# ETH_IFC.net
KiCad netlist of a schematic drawn in Altium Designer
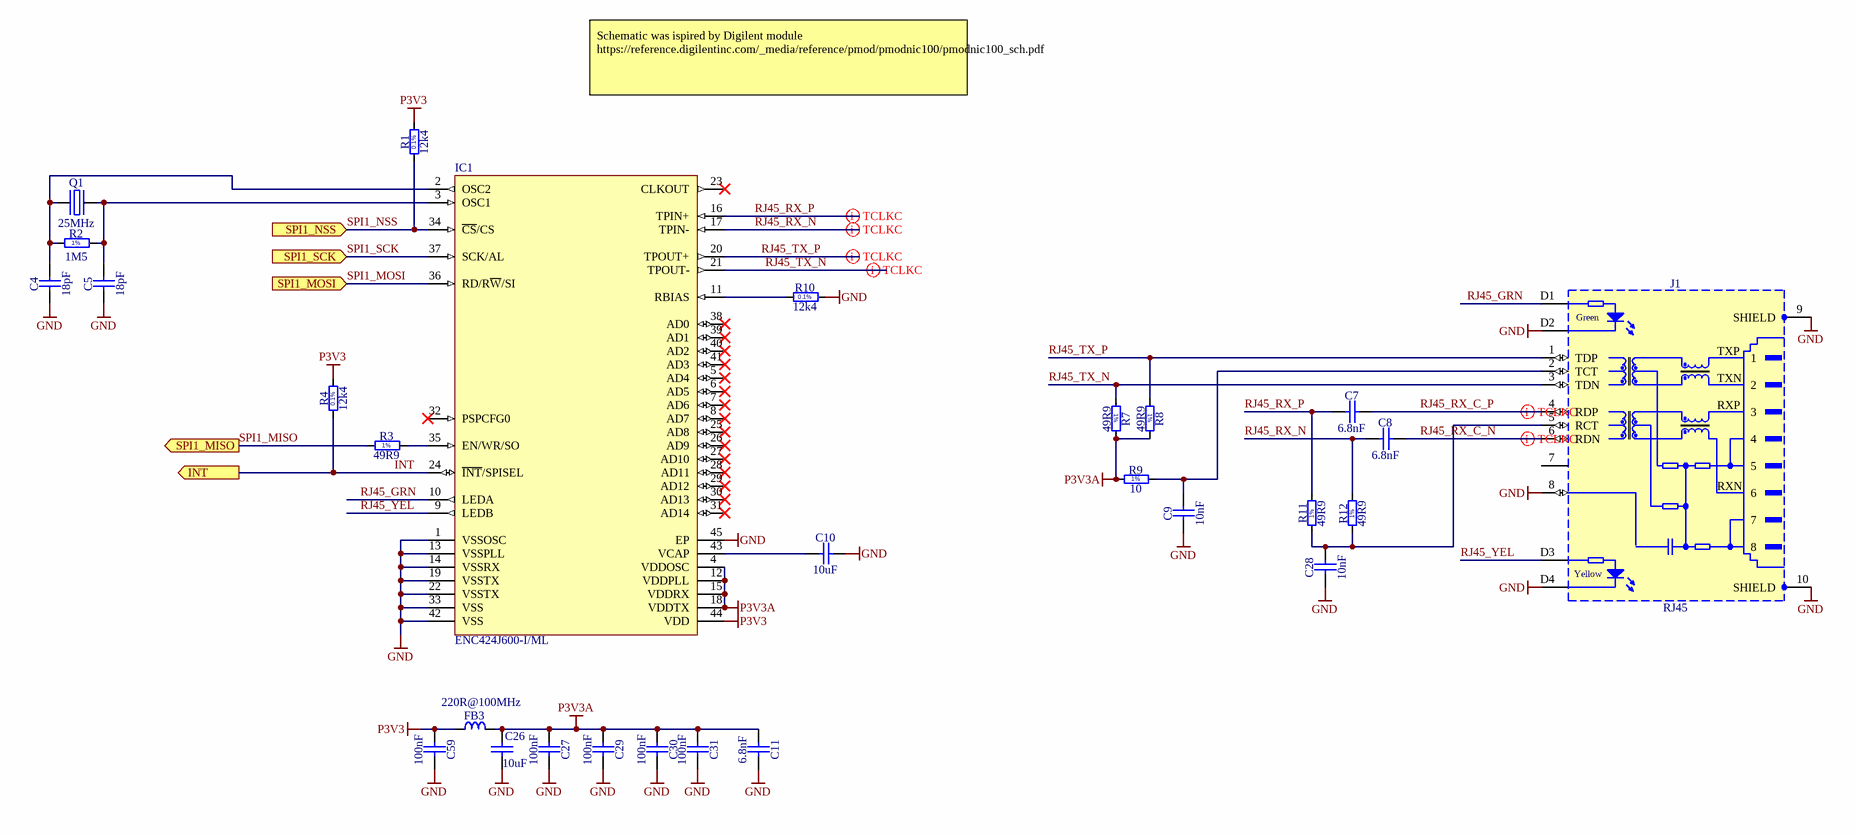
[diagram p0: ETH_IFC.SchDoc]

(export (version "E")
  (design (tool "Eeschema 10.0.6"))
  (components
    (comp (ref "C4")
      (value "18pF")
      (footprint "CAPC1005X55N")
      (description "Non-polarised capacitor")
      (fields
        (field (name "PART NUMBER") "CC0402_18PF_50V_5%_C0G")
        (field (name "VOLTAGE") "50V")
        (field (name "AUTHOR") "CERN DEM JLC")
      )
      (libsource (lib "Capacitors") (part "Capacitor - non polarized"))
    )
    (comp (ref "C5")
      (value "18pF")
      (footprint "CAPC1005X55N")
      (description "Non-polarised capacitor")
      (fields
        (field (name "PART NUMBER") "CC0402_18PF_50V_5%_C0G")
        (field (name "VOLTAGE") "50V")
        (field (name "AUTHOR") "CERN DEM JLC")
      )
      (libsource (lib "Capacitors") (part "Capacitor - non polarized"))
    )
    (comp (ref "C7")
      (value "6.8nF")
      (footprint "CAPC1608X87N")
      (description "Non-polarised capacitor")
      (fields
        (field (name "PART NUMBER") "CC0603_6.8NF_25V_1%_C0G")
        (field (name "VOLTAGE") "25V")
        (field (name "AUTHOR") "CERN DEM JLC")
      )
      (libsource (lib "Capacitors") (part "Capacitor - non polarized"))
    )
    (comp (ref "C8")
      (value "6.8nF")
      (footprint "CAPC1608X87N")
      (description "Non-polarised capacitor")
      (fields
        (field (name "PART NUMBER") "CC0603_6.8NF_25V_1%_C0G")
        (field (name "VOLTAGE") "25V")
        (field (name "AUTHOR") "CERN DEM JLC")
      )
      (libsource (lib "Capacitors") (part "Capacitor - non polarized"))
    )
    (comp (ref "C9")
      (value "10nF")
      (footprint "CAPC1608X87N")
      (description "Non-polarised capacitor")
      (fields
        (field (name "PART NUMBER") "CC0603_10NF_50V_5%_C0G")
        (field (name "VOLTAGE") "50V")
        (field (name "AUTHOR") "CERN DEM JLC")
      )
      (libsource (lib "Capacitors") (part "Capacitor - non polarized"))
    )
    (comp (ref "C10")
      (value "10uF")
      (footprint "CAPC1608X80N")
      (description "Non-polarised capacitor")
      (fields
        (field (name "PART NUMBER") "CC0603_10UF_16V_20%_X5R")
        (field (name "VOLTAGE") "16V")
        (field (name "AUTHOR") "CERN DEM MR")
      )
      (libsource (lib "Capacitors") (part "Capacitor - non polarized"))
    )
    (comp (ref "C11")
      (value "6.8nF")
      (footprint "CAPC1608X87N")
      (description "Non-polarised capacitor")
      (fields
        (field (name "PART NUMBER") "CC0603_6.8NF_25V_1%_C0G")
        (field (name "VOLTAGE") "25V")
        (field (name "AUTHOR") "CERN DEM JLC")
      )
      (libsource (lib "Capacitors") (part "Capacitor - non polarized"))
    )
    (comp (ref "C26")
      (value "10uF")
      (footprint "CAPC2012X135N")
      (description "Non-polarised capacitor")
      (fields
        (field (name "PART NUMBER") "CC0805_10UF_10V_10%_X7R")
        (field (name "VOLTAGE") "10V")
        (field (name "AUTHOR") "CERN DEM JLC")
      )
      (libsource (lib "Capacitors") (part "Capacitor - non polarized"))
    )
    (comp (ref "C27")
      (value "100nF")
      (footprint "CAPC1005X55N")
      (description "Non-polarised capacitor")
      (fields
        (field (name "PART NUMBER") "CC0402_100NF_16V_10%_X7R")
        (field (name "VOLTAGE") "16V")
        (field (name "AUTHOR") "CERN DEM JLC")
      )
      (libsource (lib "Capacitors") (part "Capacitor - non polarized"))
    )
    (comp (ref "C28")
      (value "10nF")
      (footprint "CAPC1608X87N")
      (description "Non-polarised capacitor")
      (fields
        (field (name "PART NUMBER") "CC0603_10NF_50V_5%_C0G")
        (field (name "VOLTAGE") "50V")
        (field (name "AUTHOR") "CERN DEM JLC")
      )
      (libsource (lib "Capacitors") (part "Capacitor - non polarized"))
    )
    (comp (ref "C29")
      (value "100nF")
      (footprint "CAPC1005X55N")
      (description "Non-polarised capacitor")
      (fields
        (field (name "PART NUMBER") "CC0402_100NF_16V_10%_X7R")
        (field (name "VOLTAGE") "16V")
        (field (name "AUTHOR") "CERN DEM JLC")
      )
      (libsource (lib "Capacitors") (part "Capacitor - non polarized"))
    )
    (comp (ref "C30")
      (value "100nF")
      (footprint "CAPC1005X55N")
      (description "Non-polarised capacitor")
      (fields
        (field (name "PART NUMBER") "CC0402_100NF_16V_10%_X7R")
        (field (name "VOLTAGE") "16V")
        (field (name "AUTHOR") "CERN DEM JLC")
      )
      (libsource (lib "Capacitors") (part "Capacitor - non polarized"))
    )
    (comp (ref "C31")
      (value "100nF")
      (footprint "CAPC1005X55N")
      (description "Non-polarised capacitor")
      (fields
        (field (name "PART NUMBER") "CC0402_100NF_16V_10%_X7R")
        (field (name "VOLTAGE") "16V")
        (field (name "AUTHOR") "CERN DEM JLC")
      )
      (libsource (lib "Capacitors") (part "Capacitor - non polarized"))
    )
    (comp (ref "C59")
      (value "100nF")
      (footprint "CAPC1005X55N")
      (description "Non-polarised capacitor")
      (fields
        (field (name "PART NUMBER") "CC0402_100NF_16V_10%_X7R")
        (field (name "VOLTAGE") "16V")
        (field (name "AUTHOR") "CERN DEM JLC")
      )
      (libsource (lib "Capacitors") (part "Capacitor - non polarized"))
    )
    (comp (ref "FB3")
      (value "220R@100MHz")
      (footprint "INDC2012X105N")
      (description "Inductor")
      (fields
        (field (name "PART NUMBER") "IND0805_MURATA_BLM21PG221SN1D")
        (field (name "POWER") "2A")
        (field (name "AUTHOR") "CERN DEM JLC")
      )
      (libsource (lib "Inductors & Transformers") (part "Inductor"))
    )
    (comp (ref "IC1")
      (value "ENC424J600-I/ML")
      (footprint "QFN-ML44_M")
      (libsource (lib "Altium Content Vault") (part "COM-ENET-ENC424J600-45"))
    )
    (comp (ref "J1")
      (value "RJ45")
      (footprint "TYCO_5-6605308-1")
      (fields
        (field (name "PART NUMBER") "TYCO_5-6605308-1")
        (field (name "MANUFACTURER") "TYCO ELECTRONICS")
        (field (name "MANUFACTURER PART NUMBER") "5-6605308-1")
        (field (name "AUTHOR") "CERN DEM JLC")
      )
      (libsource (lib "Connectors") (part "TYCO_5-6605308-1"))
    )
    (comp (ref "Q1")
      (value "25MHz")
      (footprint "XTAL_TXC_AA")
      (description "Quartz Crystal")
      (fields
        (field (name "PART NUMBER") "XTAL_25MHZ_TXC_AA-25.000MALE-T")
        (field (name "MANUFACTURER") "TXC CORPORATION")
        (field (name "AUTHOR") "GK")
      )
      (libsource (lib "Crystals_Oscillators") (part "XTAL_25MHZ_TXC_AA-25.000MALE-T"))
    )
    (comp (ref "R1")
      (value "12k4")
      (footprint "RESC1608X55N")
      (description "Resistor - 0.1%")
      (fields
        (field (name "PART NUMBER") "R0603_12K4_0.1%_0.063W_10PPM")
        (field (name "POWER") "0.063W")
        (field (name "AUTHOR") "CERN DEM JLC")
      )
      (libsource (lib "Resistors") (part "Resistor - 0.1%"))
    )
    (comp (ref "R2")
      (value "1M5")
      (footprint "RESC1005X40N")
      (description "Resistor - 1%")
      (fields
        (field (name "PART NUMBER") "R0402_1M5_1%_0.0625W_100PPM")
        (field (name "POWER") "0.0625W")
        (field (name "AUTHOR") "CERN DEM JLC")
      )
      (libsource (lib "Resistors") (part "Resistor - 1%"))
    )
    (comp (ref "R3")
      (value "49R9")
      (footprint "RESC1005X40N")
      (description "Resistor - 1%")
      (fields
        (field (name "PART NUMBER") "R0402_49R9_1%_0.0625W_100PPM")
        (field (name "POWER") "0.0625W")
        (field (name "AUTHOR") "CERN DEM JLC")
      )
      (libsource (lib "Resistors") (part "Resistor - 1%"))
    )
    (comp (ref "R4")
      (value "12k4")
      (footprint "RESC1608X55N")
      (description "Resistor - 0.1%")
      (fields
        (field (name "PART NUMBER") "R0603_12K4_0.1%_0.063W_10PPM")
        (field (name "POWER") "0.063W")
        (field (name "AUTHOR") "CERN DEM JLC")
      )
      (libsource (lib "Resistors") (part "Resistor - 0.1%"))
    )
    (comp (ref "R7")
      (value "49R9")
      (footprint "RESC1005X40N")
      (description "Resistor - 1%")
      (fields
        (field (name "PART NUMBER") "R0402_49R9_1%_0.0625W_100PPM")
        (field (name "POWER") "0.0625W")
        (field (name "AUTHOR") "CERN DEM JLC")
      )
      (libsource (lib "Resistors") (part "Resistor - 1%"))
    )
    (comp (ref "R8")
      (value "49R9")
      (footprint "RESC1005X40N")
      (description "Resistor - 1%")
      (fields
        (field (name "PART NUMBER") "R0402_49R9_1%_0.0625W_100PPM")
        (field (name "POWER") "0.0625W")
        (field (name "AUTHOR") "CERN DEM JLC")
      )
      (libsource (lib "Resistors") (part "Resistor - 1%"))
    )
    (comp (ref "R9")
      (value "10")
      (footprint "RESC1005X40N")
      (description "Resistor - 1%")
      (fields
        (field (name "PART NUMBER") "R0402_10R_1%_0.0625W_200PPM")
        (field (name "POWER") "0.0625W")
        (field (name "AUTHOR") "CERN DEM JLC")
      )
      (libsource (lib "Resistors") (part "Resistor - 1%"))
    )
    (comp (ref "R10")
      (value "12k4")
      (footprint "RESC1608X55N")
      (description "Resistor - 0.1%")
      (fields
        (field (name "PART NUMBER") "R0603_12K4_0.1%_0.063W_10PPM")
        (field (name "POWER") "0.063W")
        (field (name "AUTHOR") "CERN DEM JLC")
      )
      (libsource (lib "Resistors") (part "Resistor - 0.1%"))
    )
    (comp (ref "R11")
      (value "49R9")
      (footprint "RESC1005X40N")
      (description "Resistor - 1%")
      (fields
        (field (name "PART NUMBER") "R0402_49R9_1%_0.0625W_100PPM")
        (field (name "POWER") "0.0625W")
        (field (name "AUTHOR") "CERN DEM JLC")
      )
      (libsource (lib "Resistors") (part "Resistor - 1%"))
    )
    (comp (ref "R12")
      (value "49R9")
      (footprint "RESC1005X40N")
      (description "Resistor - 1%")
      (fields
        (field (name "PART NUMBER") "R0402_49R9_1%_0.0625W_100PPM")
        (field (name "POWER") "0.0625W")
        (field (name "AUTHOR") "CERN DEM JLC")
      )
      (libsource (lib "Resistors") (part "Resistor - 1%"))
    )
  )
  (nets
    (net (code "1") (name "/INT") (class "Default")
      (node (ref "IC1") (pin "24") (pinfunction "~{INT}/SPISEL_24") (pintype "bidirectional"))
      (node (ref "R4") (pin "1") (pinfunction "1_1") (pintype "passive"))
    )
    (net (code "2") (name "/RJ45_GRN") (class "Default")
      (node (ref "IC1") (pin "10") (pinfunction "LEDA_10") (pintype "output"))
      (node (ref "J1") (pin "D1") (pinfunction "D1_D1") (pintype "passive"))
    )
    (net (code "3") (name "/RJ45_RX_C_N") (class "Default")
      (node (ref "C8") (pin "2") (pinfunction "2_2") (pintype "passive"))
      (node (ref "J1") (pin "6") (pinfunction "RDN_6") (pintype "bidirectional"))
    )
    (net (code "4") (name "/RJ45_RX_C_P") (class "Default")
      (node (ref "C7") (pin "2") (pinfunction "2_2") (pintype "passive"))
      (node (ref "J1") (pin "4") (pinfunction "RDP_4") (pintype "bidirectional"))
    )
    (net (code "5") (name "/RJ45_RX_N") (class "Default")
      (node (ref "C8") (pin "1") (pinfunction "1_1") (pintype "passive"))
      (node (ref "IC1") (pin "17") (pinfunction "TPIN-_17") (pintype "input"))
      (node (ref "R12") (pin "2") (pinfunction "2_2") (pintype "passive"))
    )
    (net (code "6") (name "/RJ45_RX_P") (class "Default")
      (node (ref "C7") (pin "1") (pinfunction "1_1") (pintype "passive"))
      (node (ref "IC1") (pin "16") (pinfunction "TPIN+_16") (pintype "input"))
      (node (ref "R11") (pin "2") (pinfunction "2_2") (pintype "passive"))
    )
    (net (code "7") (name "/RJ45_TX_N") (class "Default")
      (node (ref "IC1") (pin "21") (pinfunction "TPOUT-_21") (pintype "output"))
      (node (ref "J1") (pin "3") (pinfunction "TDN_3") (pintype "bidirectional"))
      (node (ref "R7") (pin "1") (pinfunction "1_1") (pintype "passive"))
    )
    (net (code "8") (name "/RJ45_TX_P") (class "Default")
      (node (ref "IC1") (pin "20") (pinfunction "TPOUT+_20") (pintype "output"))
      (node (ref "J1") (pin "1") (pinfunction "TDP_1") (pintype "bidirectional"))
      (node (ref "R8") (pin "1") (pinfunction "1_1") (pintype "passive"))
    )
    (net (code "9") (name "/RJ45_YEL") (class "Default")
      (node (ref "IC1") (pin "9") (pinfunction "LEDB_9") (pintype "output"))
      (node (ref "J1") (pin "D3") (pinfunction "D3_D3") (pintype "passive"))
    )
    (net (code "10") (name "/SPI1_MISO") (class "Default")
      (node (ref "R3") (pin "1") (pinfunction "1_1") (pintype "passive"))
    )
    (net (code "11") (name "/SPI1_MOSI") (class "Default")
      (node (ref "IC1") (pin "36") (pinfunction "RD/R~{W}/SI_36") (pintype "input"))
    )
    (net (code "12") (name "/SPI1_NSS") (class "Default")
      (node (ref "IC1") (pin "34") (pinfunction "~{CS}/CS_34") (pintype "input"))
      (node (ref "R1") (pin "1") (pinfunction "1_1") (pintype "passive"))
    )
    (net (code "13") (name "/SPI1_SCK") (class "Default")
      (node (ref "IC1") (pin "37") (pinfunction "SCK/AL_37") (pintype "input"))
    )
    (net (code "14") (name "GND") (class "Default")
      (node (ref "C10") (pin "2") (pinfunction "2_2") (pintype "passive"))
      (node (ref "C11") (pin "2") (pinfunction "2_2") (pintype "passive"))
      (node (ref "C26") (pin "2") (pinfunction "2_2") (pintype "passive"))
      (node (ref "C27") (pin "2") (pinfunction "2_2") (pintype "passive"))
      (node (ref "C28") (pin "1") (pinfunction "1_1") (pintype "passive"))
      (node (ref "C29") (pin "2") (pinfunction "2_2") (pintype "passive"))
      (node (ref "C30") (pin "2") (pinfunction "2_2") (pintype "passive"))
      (node (ref "C31") (pin "2") (pinfunction "2_2") (pintype "passive"))
      (node (ref "C4") (pin "1") (pinfunction "1_1") (pintype "passive"))
      (node (ref "C5") (pin "1") (pinfunction "1_1") (pintype "passive"))
      (node (ref "C59") (pin "2") (pinfunction "2_2") (pintype "passive"))
      (node (ref "C9") (pin "1") (pinfunction "1_1") (pintype "passive"))
      (node (ref "IC1") (pin "1") (pinfunction "VSSOSC_1") (pintype "power_in"))
      (node (ref "IC1") (pin "13") (pinfunction "VSSPLL_13") (pintype "power_in"))
      (node (ref "IC1") (pin "14") (pinfunction "VSSRX_14") (pintype "power_in"))
      (node (ref "IC1") (pin "19") (pinfunction "VSSTX_19") (pintype "power_in"))
      (node (ref "IC1") (pin "22") (pinfunction "VSSTX_22") (pintype "power_in"))
      (node (ref "IC1") (pin "33") (pinfunction "VSS_33") (pintype "power_in"))
      (node (ref "IC1") (pin "42") (pinfunction "VSS_42") (pintype "power_in"))
      (node (ref "IC1") (pin "45") (pinfunction "EP_45") (pintype "passive"))
      (node (ref "J1") (pin "10") (pinfunction "SHIELD_10") (pintype "power_in"))
      (node (ref "J1") (pin "8") (pinfunction "8_8") (pintype "bidirectional"))
      (node (ref "J1") (pin "9") (pinfunction "SHIELD_9") (pintype "power_in"))
      (node (ref "J1") (pin "D2") (pinfunction "D2_D2") (pintype "passive"))
      (node (ref "J1") (pin "D4") (pinfunction "D4_D4") (pintype "passive"))
      (node (ref "R10") (pin "2") (pinfunction "2_2") (pintype "passive"))
    )
    (net (code "15") (name "Net-(IC1-EN{slash}WR{slash}SO)") (class "Default")
      (node (ref "IC1") (pin "35") (pinfunction "EN/WR/SO_35") (pintype "input"))
      (node (ref "R3") (pin "2") (pinfunction "2_2") (pintype "passive"))
    )
    (net (code "16") (name "Net-(IC1-OSC1)") (class "Default")
      (node (ref "C5") (pin "2") (pinfunction "2_2") (pintype "passive"))
      (node (ref "IC1") (pin "3") (pinfunction "OSC1_3") (pintype "input"))
      (node (ref "Q1") (pin "2") (pinfunction "OSC2_2") (pintype "passive"))
      (node (ref "R2") (pin "2") (pinfunction "2_2") (pintype "passive"))
    )
    (net (code "17") (name "Net-(IC1-OSC2)") (class "Default")
      (node (ref "C4") (pin "2") (pinfunction "2_2") (pintype "passive"))
      (node (ref "IC1") (pin "2") (pinfunction "OSC2_2") (pintype "output"))
      (node (ref "Q1") (pin "1") (pinfunction "OSC1_1") (pintype "passive"))
      (node (ref "R2") (pin "1") (pinfunction "1_1") (pintype "passive"))
    )
    (net (code "18") (name "Net-(IC1-RBIAS)") (class "Default")
      (node (ref "IC1") (pin "11") (pinfunction "RBIAS_11") (pintype "input"))
      (node (ref "R10") (pin "1") (pinfunction "1_1") (pintype "passive"))
    )
    (net (code "19") (name "Net-(IC1-VCAP)") (class "Default")
      (node (ref "C10") (pin "1") (pinfunction "1_1") (pintype "passive"))
      (node (ref "IC1") (pin "43") (pinfunction "VCAP_43") (pintype "power_in"))
    )
    (net (code "20") (name "Net-(J1-RCT)") (class "Default")
      (node (ref "C28") (pin "2") (pinfunction "2_2") (pintype "passive"))
      (node (ref "J1") (pin "5") (pinfunction "RCT_5") (pintype "bidirectional"))
      (node (ref "R11") (pin "1") (pinfunction "1_1") (pintype "passive"))
      (node (ref "R12") (pin "1") (pinfunction "1_1") (pintype "passive"))
    )
    (net (code "21") (name "Net-(J1-TCT)") (class "Default")
      (node (ref "C9") (pin "2") (pinfunction "2_2") (pintype "passive"))
      (node (ref "J1") (pin "2") (pinfunction "TCT_2") (pintype "bidirectional"))
      (node (ref "R9") (pin "2") (pinfunction "2_2") (pintype "passive"))
    )
    (net (code "22") (name "P3V3") (class "Default")
      (node (ref "C59") (pin "1") (pinfunction "1_1") (pintype "passive"))
      (node (ref "FB3") (pin "1") (pinfunction "1_1") (pintype "passive"))
      (node (ref "IC1") (pin "44") (pinfunction "VDD_44") (pintype "power_in"))
      (node (ref "R1") (pin "2") (pinfunction "2_2") (pintype "passive"))
      (node (ref "R4") (pin "2") (pinfunction "2_2") (pintype "passive"))
    )
    (net (code "23") (name "P3V3A") (class "Default")
      (node (ref "C11") (pin "1") (pinfunction "1_1") (pintype "passive"))
      (node (ref "C26") (pin "1") (pinfunction "1_1") (pintype "passive"))
      (node (ref "C27") (pin "1") (pinfunction "1_1") (pintype "passive"))
      (node (ref "C29") (pin "1") (pinfunction "1_1") (pintype "passive"))
      (node (ref "C30") (pin "1") (pinfunction "1_1") (pintype "passive"))
      (node (ref "C31") (pin "1") (pinfunction "1_1") (pintype "passive"))
      (node (ref "FB3") (pin "2") (pinfunction "2_2") (pintype "passive"))
      (node (ref "IC1") (pin "12") (pinfunction "VDDPLL_12") (pintype "power_in"))
      (node (ref "IC1") (pin "15") (pinfunction "VDDRX_15") (pintype "power_in"))
      (node (ref "IC1") (pin "18") (pinfunction "VDDTX_18") (pintype "power_in"))
      (node (ref "IC1") (pin "4") (pinfunction "VDDOSC_4") (pintype "power_in"))
      (node (ref "R7") (pin "2") (pinfunction "2_2") (pintype "passive"))
      (node (ref "R8") (pin "2") (pinfunction "2_2") (pintype "passive"))
      (node (ref "R9") (pin "1") (pinfunction "1_1") (pintype "passive"))
    )
    (net (code "24") (name "unconnected-(IC1-AD0-Pad38)") (class "Default")
      (node (ref "IC1") (pin "38") (pinfunction "AD0_38") (pintype "bidirectional+no_connect"))
    )
    (net (code "25") (name "unconnected-(IC1-AD1-Pad39)") (class "Default")
      (node (ref "IC1") (pin "39") (pinfunction "AD1_39") (pintype "bidirectional+no_connect"))
    )
    (net (code "26") (name "unconnected-(IC1-AD2-Pad40)") (class "Default")
      (node (ref "IC1") (pin "40") (pinfunction "AD2_40") (pintype "bidirectional+no_connect"))
    )
    (net (code "27") (name "unconnected-(IC1-AD3-Pad41)") (class "Default")
      (node (ref "IC1") (pin "41") (pinfunction "AD3_41") (pintype "bidirectional+no_connect"))
    )
    (net (code "28") (name "unconnected-(IC1-AD4-Pad5)") (class "Default")
      (node (ref "IC1") (pin "5") (pinfunction "AD4_5") (pintype "bidirectional+no_connect"))
    )
    (net (code "29") (name "unconnected-(IC1-AD5-Pad6)") (class "Default")
      (node (ref "IC1") (pin "6") (pinfunction "AD5_6") (pintype "bidirectional+no_connect"))
    )
    (net (code "30") (name "unconnected-(IC1-AD6-Pad7)") (class "Default")
      (node (ref "IC1") (pin "7") (pinfunction "AD6_7") (pintype "bidirectional+no_connect"))
    )
    (net (code "31") (name "unconnected-(IC1-AD7-Pad8)") (class "Default")
      (node (ref "IC1") (pin "8") (pinfunction "AD7_8") (pintype "bidirectional+no_connect"))
    )
    (net (code "32") (name "unconnected-(IC1-AD8-Pad25)") (class "Default")
      (node (ref "IC1") (pin "25") (pinfunction "AD8_25") (pintype "bidirectional+no_connect"))
    )
    (net (code "33") (name "unconnected-(IC1-AD9-Pad26)") (class "Default")
      (node (ref "IC1") (pin "26") (pinfunction "AD9_26") (pintype "bidirectional+no_connect"))
    )
    (net (code "34") (name "unconnected-(IC1-AD10-Pad27)") (class "Default")
      (node (ref "IC1") (pin "27") (pinfunction "AD10_27") (pintype "bidirectional+no_connect"))
    )
    (net (code "35") (name "unconnected-(IC1-AD11-Pad28)") (class "Default")
      (node (ref "IC1") (pin "28") (pinfunction "AD11_28") (pintype "bidirectional+no_connect"))
    )
    (net (code "36") (name "unconnected-(IC1-AD12-Pad29)") (class "Default")
      (node (ref "IC1") (pin "29") (pinfunction "AD12_29") (pintype "bidirectional+no_connect"))
    )
    (net (code "37") (name "unconnected-(IC1-AD13-Pad30)") (class "Default")
      (node (ref "IC1") (pin "30") (pinfunction "AD13_30") (pintype "bidirectional+no_connect"))
    )
    (net (code "38") (name "unconnected-(IC1-AD14-Pad31)") (class "Default")
      (node (ref "IC1") (pin "31") (pinfunction "AD14_31") (pintype "bidirectional+no_connect"))
    )
    (net (code "39") (name "unconnected-(IC1-CLKOUT-Pad23)") (class "Default")
      (node (ref "IC1") (pin "23") (pinfunction "CLKOUT_23") (pintype "output+no_connect"))
    )
    (net (code "40") (name "unconnected-(IC1-PSPCFG0-Pad32)") (class "Default")
      (node (ref "IC1") (pin "32") (pinfunction "PSPCFG0_32") (pintype "input+no_connect"))
    )
    (net (code "41") (name "unconnected-(J1-Pad7)") (class "Default")
      (node (ref "J1") (pin "7") (pinfunction "7_7") (pintype "passive"))
    )
  )
)
